# Sheet1.net
KiCad netlist of a schematic drawn in Altium Designer
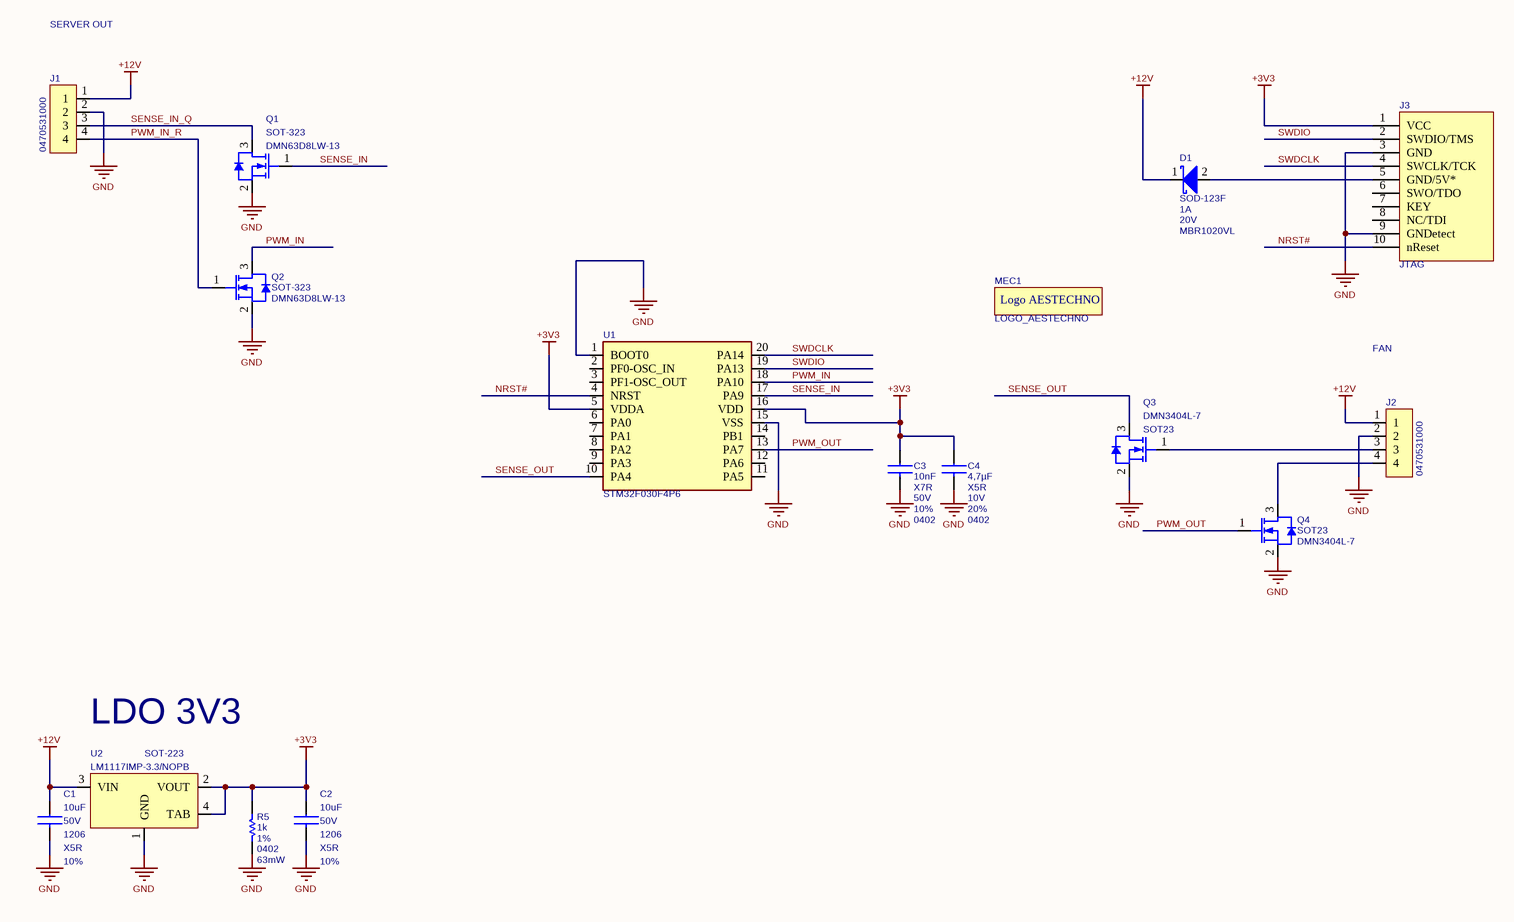
[diagram p0: Sheet1.SchDoc]

(export (version "E")
  (design (tool "Eeschema 10.0.6"))
  (components
    (comp (ref "C1")
      (value "10uF")
      (footprint "CAP_1206_180_M")
      (description "CAP CER 10uF 50V 1206 X5R")
      (fields
        (field (name "MANUFACTURER") "Samsung")
        (field (name "MANUFACTURER PART NUMBER") "CL31A106KBHNNNE")
        (field (name "TOLERANCE") "10%")
        (field (name "VOLTAGE RATING") "50V")
        (field (name "DIELECTRIC") "X5R")
        (field (name "CASE/PACKAGE") "1206")
      )
      (libsource (lib "ho schematics") (part "CAP_10uF_1206_50V_X5R"))
    )
    (comp (ref "C2")
      (value "10uF")
      (footprint "CAP_1206_180_M")
      (description "CAP CER 10uF 50V 1206 X5R")
      (fields
        (field (name "MANUFACTURER") "Samsung")
        (field (name "MANUFACTURER PART NUMBER") "CL31A106KBHNNNE")
        (field (name "TOLERANCE") "10%")
        (field (name "VOLTAGE RATING") "50V")
        (field (name "DIELECTRIC") "X5R")
        (field (name "CASE/PACKAGE") "1206")
      )
      (libsource (lib "ho schematics") (part "CAP_10uF_1206_50V_X5R"))
    )
    (comp (ref "C3")
      (value "10nF")
      (footprint "CAP_0402_60_M")
      (description "CAP CER 10nF 50V 0402 X7R")
      (fields
        (field (name "MANUFACTURER") "Samsung")
        (field (name "MANUFACTURER PART NUMBER") "CL05B103KB5NNNC")
        (field (name "DIELECTRIC") "X7R")
        (field (name "VOLTAGE") "50V")
        (field (name "TOLERANCE") "10%")
        (field (name "CASE/PACKAGE") "0402")
      )
      (libsource (lib "ho schematics") (part "CAP_10nF_0402_50V_X7R"))
    )
    (comp (ref "C4")
      (value "4,7µF")
      (footprint "CAP_0402_70_M")
      (description "CAP CER 4.7uF 10V X5R 0402")
      (fields
        (field (name "MANUFACTURER") "Murata")
        (field (name "MANUFACTURER PART NUMBER") "GRM155R61A475MEAAD")
        (field (name "DIELECTRIC") "X5R")
        (field (name "VOLTAGE") "10V")
        (field (name "TOLERANCE") "20%")
        (field (name "CASE/PACKAGE") "0402")
      )
      (libsource (lib "ho schematics") (part "CAP_4.7uF_0402_10V_X5R"))
    )
    (comp (ref "D1")
      (value "SOD-123F")
      (footprint "SOD-123FL")
      (description "DIODE SCHOTTKY 20V 1A SOD-123F")
      (fields
        (field (name "MANUFACTURER") "ON Semiconductor / Fairchild")
        (field (name "AVERAGE RECTIFIED CURRENT") "1A")
        (field (name "MAX REPETITIVE REVERSE VOLTAGE (VRRM)") "20V")
        (field (name "MANUFACTURER PART NUMBER") "MBR1020VL")
      )
      (libsource (lib "ho schematics") (part "DIO_SCHOTTKY_1A_20V_SOD_123F"))
    )
    (comp (ref "J1")
      (value "CON_4PTS_2.54mm_KK_FAN")
      (footprint "CON_4PTS_KK_FAN")
      (description "CONN HEADER VERT 4POS 2.54MM")
      (fields (field (name "MANUFACTURER") "Molex") (field (name "MANUFACTURER PART NUMBER") "0470531000"))
      (libsource (lib "ho schematics") (part "CON_4PTS_2.54mm_KK_FAN"))
    )
    (comp (ref "J2")
      (value "CON_4PTS_2.54mm_KK_FAN")
      (footprint "CON_4PTS_KK_FAN")
      (description "CONN HEADER VERT 4POS 2.54MM")
      (fields (field (name "MANUFACTURER") "Molex") (field (name "MANUFACTURER PART NUMBER") "0470531000"))
      (libsource (lib "") (part "CON_4PTS_2.54mm_KK_FAN_1"))
    )
    (comp (ref "J3")
      (value "JTAG")
      (footprint "TC2050_DUAL")
      (description "JTAG CONNECTOR")
      (libsource (lib "ho schematics") (part "TC2050_DUAL"))
    )
    (comp (ref "MEC1")
      (value "LOGO_AESTECHNO")
      (footprint "Logo_AESTECHNO")
      (description "LOGO AESTECNO")
      (libsource (lib "ho schematics") (part "LOGO_AESTECHNO"))
    )
    (comp (ref "Q1")
      (value "SOT-323")
      (footprint "SOT-323")
      (description "MOSFET N-CH 30V 0.38A SOT323")
      (fields (field (name "MANUFACTURER") "Diodes") (field (name "MANUFACTURER PART NUMBER") "DMN63D8LW-13"))
      (libsource (lib "ho schematics") (part "TRS_NMOS_30V_0.38A_DMN63D8LW-13"))
    )
    (comp (ref "Q2")
      (value "SOT-323")
      (footprint "SOT-323")
      (description "MOSFET N-CH 30V 0.38A SOT323")
      (fields (field (name "MANUFACTURER") "Diodes") (field (name "MANUFACTURER PART NUMBER") "DMN63D8LW-13"))
      (libsource (lib "ho schematics") (part "TRS_NMOS_30V_0.38A_DMN63D8LW-13"))
    )
    (comp (ref "Q3")
      (value "SOT23")
      (footprint "SOT-23")
      (description "Small Signal Field-Effect Transistor")
      (fields (field (name "MANUFACTURER") "Diodes") (field (name "MANUFACTURER PART NUMBER") "DMN3404L-7"))
      (libsource (lib "ho schematics") (part "TRS_NMOS_30V_5.8AA_DMN3404L-7_SOT23"))
    )
    (comp (ref "Q4")
      (value "SOT23")
      (footprint "SOT-23")
      (description "Small Signal Field-Effect Transistor")
      (fields (field (name "MANUFACTURER") "Diodes") (field (name "MANUFACTURER PART NUMBER") "DMN3404L-7"))
      (libsource (lib "ho schematics") (part "TRS_NMOS_30V_5.8AA_DMN3404L-7_SOT23"))
    )
    (comp (ref "R5")
      (value "1k")
      (footprint "RES_0402_35_M")
      (description "RES 1k 62.5mW 1% 0402")
      (fields
        (field (name "MANUFACTURER") "Yageo")
        (field (name "MANUFACTURER PART NUMBER") "RC0402FR-071KL")
        (field (name "TOLERANCE") "1%")
        (field (name "CASE/PACKAGE") "0402")
        (field (name "POWER RATING") "63mW")
      )
      (libsource (lib "ho schematics") (part "RES_1K_62.5mW_1%_0402"))
    )
    (comp (ref "U1")
      (value "STM32F030F4P6")
      (footprint "TSSOP20-65P-650X440")
      (description "ARM® Cortex®-M0 STM32F0 Microcontroller IC 32-Bit Single-Core 48MHz 16KB (16K x 8) FLASH 20-TSSOP")
      (fields
        (field (name "MANUFACTURER_PART_NUMBER") "STM32F030F4P6TR")
        (field (name "PARTNUMBER") "1000044559")
      )
      (libsource (lib "AES-E003-LIB005") (part "STM32F030F4P6"))
    )
    (comp (ref "U2")
      (value "LM1117IMP-3.3/NOPB")
      (footprint "SOT-223")
      (description "REG LDO 3V3 800mA")
      (fields
        (field (name "MANUFACTURER") "Texas Instruments")
        (field (name "CASE/PACKAGE") "SOT-223")
        (field (name "MANUFACTURER PART NUMBER") "LM1117IMPX-3.3/NOPB")
      )
      (libsource (lib "ho schematics") (part "CIN_REG_LDO_3V3_800mA_SOT-223"))
    )
  )
  (nets
    (net (code "1") (name "+3V3") (class "Default")
      (node (ref "C2") (pin "1") (pinfunction "1_1") (pintype "passive"))
      (node (ref "C3") (pin "1") (pinfunction "1_1") (pintype "passive"))
      (node (ref "C4") (pin "1") (pinfunction "1_1") (pintype "passive"))
      (node (ref "J3") (pin "1") (pinfunction "VCC_1") (pintype "power_in"))
      (node (ref "R5") (pin "2") (pinfunction "P2_2") (pintype "passive"))
      (node (ref "U1") (pin "16") (pinfunction "VDD_16") (pintype "passive"))
      (node (ref "U1") (pin "5") (pinfunction "VDDA_5") (pintype "passive"))
      (node (ref "U2") (pin "2") (pinfunction "VOUT_2") (pintype "passive"))
      (node (ref "U2") (pin "4") (pinfunction "TAB_4") (pintype "passive"))
    )
    (net (code "2") (name "+12V") (class "Default")
      (node (ref "C1") (pin "1") (pinfunction "1_1") (pintype "passive"))
      (node (ref "D1") (pin "1") (pinfunction "K_1") (pintype "passive"))
      (node (ref "J1") (pin "1") (pinfunction "1_1") (pintype "passive"))
      (node (ref "J2") (pin "1") (pinfunction "1_1") (pintype "passive"))
      (node (ref "U2") (pin "3") (pinfunction "VIN_3") (pintype "passive"))
    )
    (net (code "3") (name "/NRST#") (class "Default")
      (node (ref "J3") (pin "10") (pinfunction "nReset_10") (pintype "passive"))
      (node (ref "U1") (pin "4") (pinfunction "NRST_4") (pintype "passive"))
    )
    (net (code "4") (name "/PWM_IN") (class "Default")
      (node (ref "Q2") (pin "3") (pinfunction "D_3") (pintype "passive"))
      (node (ref "U1") (pin "18") (pinfunction "PA10_18") (pintype "passive"))
    )
    (net (code "5") (name "/PWM_IN_R") (class "Default")
      (node (ref "J1") (pin "4") (pinfunction "4_4") (pintype "passive"))
      (node (ref "Q2") (pin "1") (pinfunction "G_1") (pintype "passive"))
    )
    (net (code "6") (name "/PWM_OUT") (class "Default")
      (node (ref "Q4") (pin "1") (pinfunction "G_1") (pintype "passive"))
      (node (ref "U1") (pin "13") (pinfunction "PA7_13") (pintype "passive"))
    )
    (net (code "7") (name "/SENSE_IN") (class "Default")
      (node (ref "Q1") (pin "1") (pinfunction "G_1") (pintype "passive"))
      (node (ref "U1") (pin "17") (pinfunction "PA9_17") (pintype "passive"))
    )
    (net (code "8") (name "/SENSE_IN_Q") (class "Default")
      (node (ref "J1") (pin "3") (pinfunction "3_3") (pintype "passive"))
      (node (ref "Q1") (pin "3") (pinfunction "D_3") (pintype "passive"))
    )
    (net (code "9") (name "/SENSE_OUT") (class "Default")
      (node (ref "Q3") (pin "3") (pinfunction "D_3") (pintype "passive"))
      (node (ref "U1") (pin "10") (pinfunction "PA4_10") (pintype "passive"))
    )
    (net (code "10") (name "/SWDCLK") (class "Default")
      (node (ref "J3") (pin "4") (pinfunction "SWCLK/TCK_4") (pintype "passive"))
      (node (ref "U1") (pin "20") (pinfunction "PA14_20") (pintype "passive"))
    )
    (net (code "11") (name "/SWDIO") (class "Default")
      (node (ref "J3") (pin "2") (pinfunction "SWDIO/TMS_2") (pintype "passive"))
      (node (ref "U1") (pin "19") (pinfunction "PA13_19") (pintype "passive"))
    )
    (net (code "12") (name "GND") (class "Default")
      (node (ref "C1") (pin "2") (pinfunction "2_2") (pintype "passive"))
      (node (ref "C2") (pin "2") (pinfunction "2_2") (pintype "passive"))
      (node (ref "C3") (pin "2") (pinfunction "2_2") (pintype "passive"))
      (node (ref "C4") (pin "2") (pinfunction "2_2") (pintype "passive"))
      (node (ref "J1") (pin "2") (pinfunction "2_2") (pintype "passive"))
      (node (ref "J2") (pin "2") (pinfunction "2_2") (pintype "passive"))
      (node (ref "J3") (pin "3") (pinfunction "GND_3") (pintype "passive"))
      (node (ref "J3") (pin "9") (pinfunction "GNDetect_9") (pintype "passive"))
      (node (ref "Q1") (pin "2") (pinfunction "S_2") (pintype "passive"))
      (node (ref "Q2") (pin "2") (pinfunction "S_2") (pintype "passive"))
      (node (ref "Q3") (pin "2") (pinfunction "S_2") (pintype "passive"))
      (node (ref "Q4") (pin "2") (pinfunction "S_2") (pintype "passive"))
      (node (ref "R5") (pin "1") (pinfunction "P1_1") (pintype "passive"))
      (node (ref "U1") (pin "1") (pinfunction "BOOT0_1") (pintype "passive"))
      (node (ref "U1") (pin "15") (pinfunction "VSS_15") (pintype "passive"))
      (node (ref "U2") (pin "1") (pinfunction "GND_1") (pintype "passive"))
    )
    (net (code "13") (name "Net-(D1-A)") (class "Default")
      (node (ref "D1") (pin "2") (pinfunction "A_2") (pintype "passive"))
      (node (ref "J3") (pin "5") (pinfunction "GND/5V*_5") (pintype "passive"))
    )
    (net (code "14") (name "Net-(Q3-G)") (class "Default")
      (node (ref "J2") (pin "3") (pinfunction "3_3") (pintype "passive"))
      (node (ref "Q3") (pin "1") (pinfunction "G_1") (pintype "passive"))
    )
    (net (code "15") (name "Net-(Q4-D)") (class "Default")
      (node (ref "J2") (pin "4") (pinfunction "4_4") (pintype "passive"))
      (node (ref "Q4") (pin "3") (pinfunction "D_3") (pintype "passive"))
    )
    (net (code "16") (name "unconnected-(J3-KEY-Pad7)") (class "Default")
      (node (ref "J3") (pin "7") (pinfunction "KEY_7") (pintype "passive"))
    )
    (net (code "17") (name "unconnected-(J3-NC{slash}TDI-Pad8)") (class "Default")
      (node (ref "J3") (pin "8") (pinfunction "NC/TDI_8") (pintype "passive"))
    )
    (net (code "18") (name "unconnected-(J3-SWO{slash}TDO-Pad6)") (class "Default")
      (node (ref "J3") (pin "6") (pinfunction "SWO/TDO_6") (pintype "passive"))
    )
    (net (code "19") (name "unconnected-(U1-PA0-Pad6)") (class "Default")
      (node (ref "U1") (pin "6") (pinfunction "PA0_6") (pintype "passive"))
    )
    (net (code "20") (name "unconnected-(U1-PA1-Pad7)") (class "Default")
      (node (ref "U1") (pin "7") (pinfunction "PA1_7") (pintype "passive"))
    )
    (net (code "21") (name "unconnected-(U1-PA2-Pad8)") (class "Default")
      (node (ref "U1") (pin "8") (pinfunction "PA2_8") (pintype "passive"))
    )
    (net (code "22") (name "unconnected-(U1-PA3-Pad9)") (class "Default")
      (node (ref "U1") (pin "9") (pinfunction "PA3_9") (pintype "passive"))
    )
    (net (code "23") (name "unconnected-(U1-PA5-Pad11)") (class "Default")
      (node (ref "U1") (pin "11") (pinfunction "PA5_11") (pintype "passive"))
    )
    (net (code "24") (name "unconnected-(U1-PA6-Pad12)") (class "Default")
      (node (ref "U1") (pin "12") (pinfunction "PA6_12") (pintype "passive"))
    )
    (net (code "25") (name "unconnected-(U1-PB1-Pad14)") (class "Default")
      (node (ref "U1") (pin "14") (pinfunction "PB1_14") (pintype "passive"))
    )
    (net (code "26") (name "unconnected-(U1-PF0-OSC_IN-Pad2)") (class "Default")
      (node (ref "U1") (pin "2") (pinfunction "PF0-OSC_IN_2") (pintype "passive"))
    )
    (net (code "27") (name "unconnected-(U1-PF1-OSC_OUT-Pad3)") (class "Default")
      (node (ref "U1") (pin "3") (pinfunction "PF1-OSC_OUT_3") (pintype "passive"))
    )
  )
)
